# INA180_Breakout.net
KiCad netlist of a schematic drawn in Altium Designer
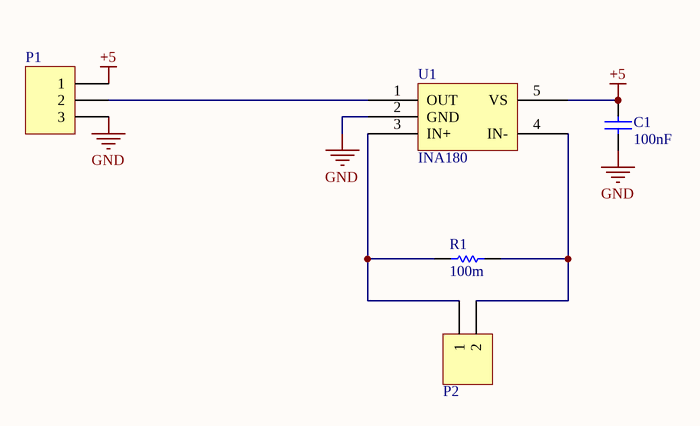
[diagram p0: INA180_Breakout.SchDoc]

(export (version "E")
  (design (tool "Eeschema 10.0.6"))
  (components
    (comp (ref "C1")
      (value "100nF")
      (footprint "0805 - Capacitor")
      (description "Nonpolarized Capacitor")
      (fields
        (field (name "MANUFACTURER") "Yageo")
        (field (name "MANUFACTURER PART NUMBER") "CC0805KRX7R9BB104")
      )
      (libsource (lib "General") (part "Capacitor - Nonpolarized"))
    )
    (comp (ref "P1")
      (value "1x3 Header")
      (footprint "HDR1X3")
      (description "1x3 Pin Header")
      (libsource (lib "GeneralConnectors") (part "1x3 Header"))
    )
    (comp (ref "P2")
      (value "1x2 Header")
      (footprint "HDR1X2")
      (description "1x2 Pin Header")
      (libsource (lib "GeneralConnectors") (part "1x2 Header"))
    )
    (comp (ref "R1")
      (value "100m")
      (footprint "0805 - Resistor")
      (description "Resistor")
      (fields (field (name "MANUFACTURER PART NUMBER") "73L3R10J") (field (name "MANUFACTURER") "CTS"))
      (libsource (lib "General") (part "Resistor"))
    )
    (comp (ref "U1")
      (value "INA180")
      (footprint "INA180")
      (description "0V to 26V Current Sense Amplifier")
      (fields
        (field (name "MANUFACTURER") "Texas Instruments")
        (field (name "MANUFACTURER PART NUMBER") "INA180A2IDBVR")
      )
      (libsource (lib "GeneralComponents") (part "INA180"))
    )
  )
  (nets
    (net (code "1") (name "+5") (class "Default")
      (node (ref "C1") (pin "2") (pinfunction "2_2") (pintype "passive"))
      (node (ref "P1") (pin "1") (pinfunction "1_1") (pintype "passive"))
      (node (ref "U1") (pin "5") (pinfunction "VS_5") (pintype "passive"))
    )
    (net (code "2") (name "GND") (class "Default")
      (node (ref "C1") (pin "1") (pinfunction "1_1") (pintype "passive"))
      (node (ref "P1") (pin "3") (pinfunction "3_3") (pintype "passive"))
      (node (ref "U1") (pin "2") (pinfunction "GND_2") (pintype "passive"))
    )
    (net (code "3") (name "Net-(U1-IN+)") (class "Default")
      (node (ref "P2") (pin "1") (pinfunction "1_1") (pintype "passive"))
      (node (ref "R1") (pin "1") (pinfunction "1_1") (pintype "passive"))
      (node (ref "U1") (pin "3") (pinfunction "IN+_3") (pintype "passive"))
    )
    (net (code "4") (name "Net-(U1-IN-)") (class "Default")
      (node (ref "P2") (pin "2") (pinfunction "2_2") (pintype "passive"))
      (node (ref "R1") (pin "2") (pinfunction "2_2") (pintype "passive"))
      (node (ref "U1") (pin "4") (pinfunction "IN-_4") (pintype "passive"))
    )
    (net (code "5") (name "Net-(U1-OUT)") (class "Default")
      (node (ref "P1") (pin "2") (pinfunction "2_2") (pintype "passive"))
      (node (ref "U1") (pin "1") (pinfunction "OUT_1") (pintype "passive"))
    )
  )
)
